# 28_PINS_PROJECT_Sheet1.net
KiCad netlist of a schematic drawn in Altium Designer
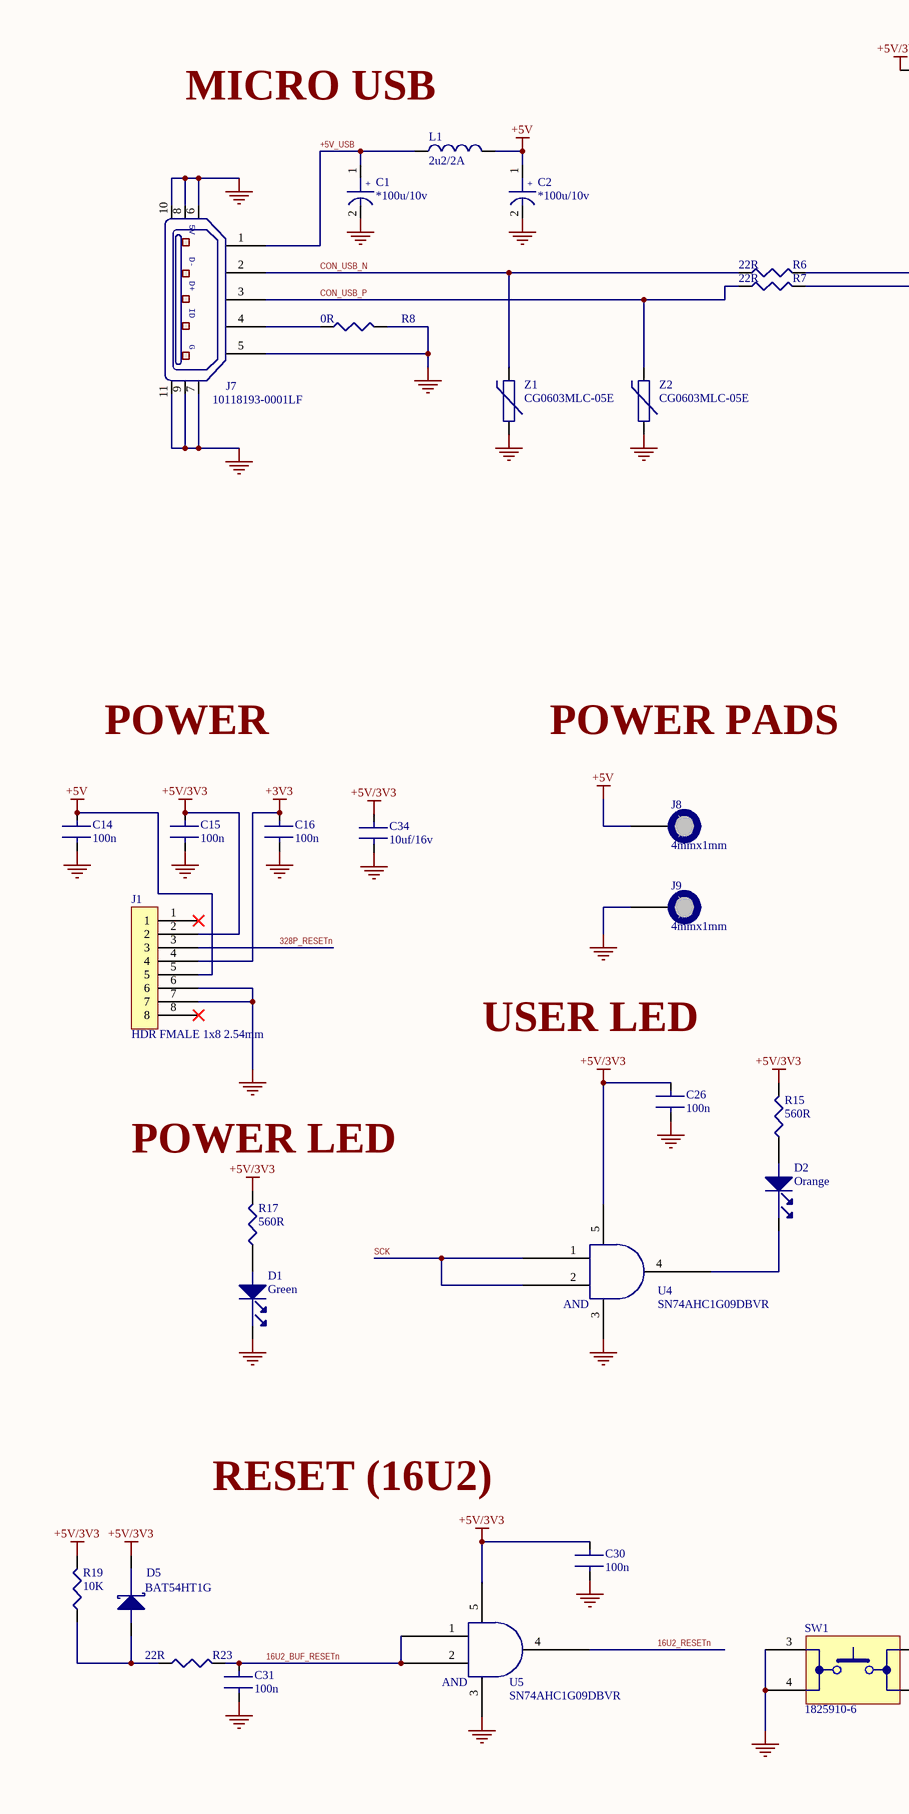
[diagram p0: 28_PINS_PROJECT_Sheet1.SchDoc, left]
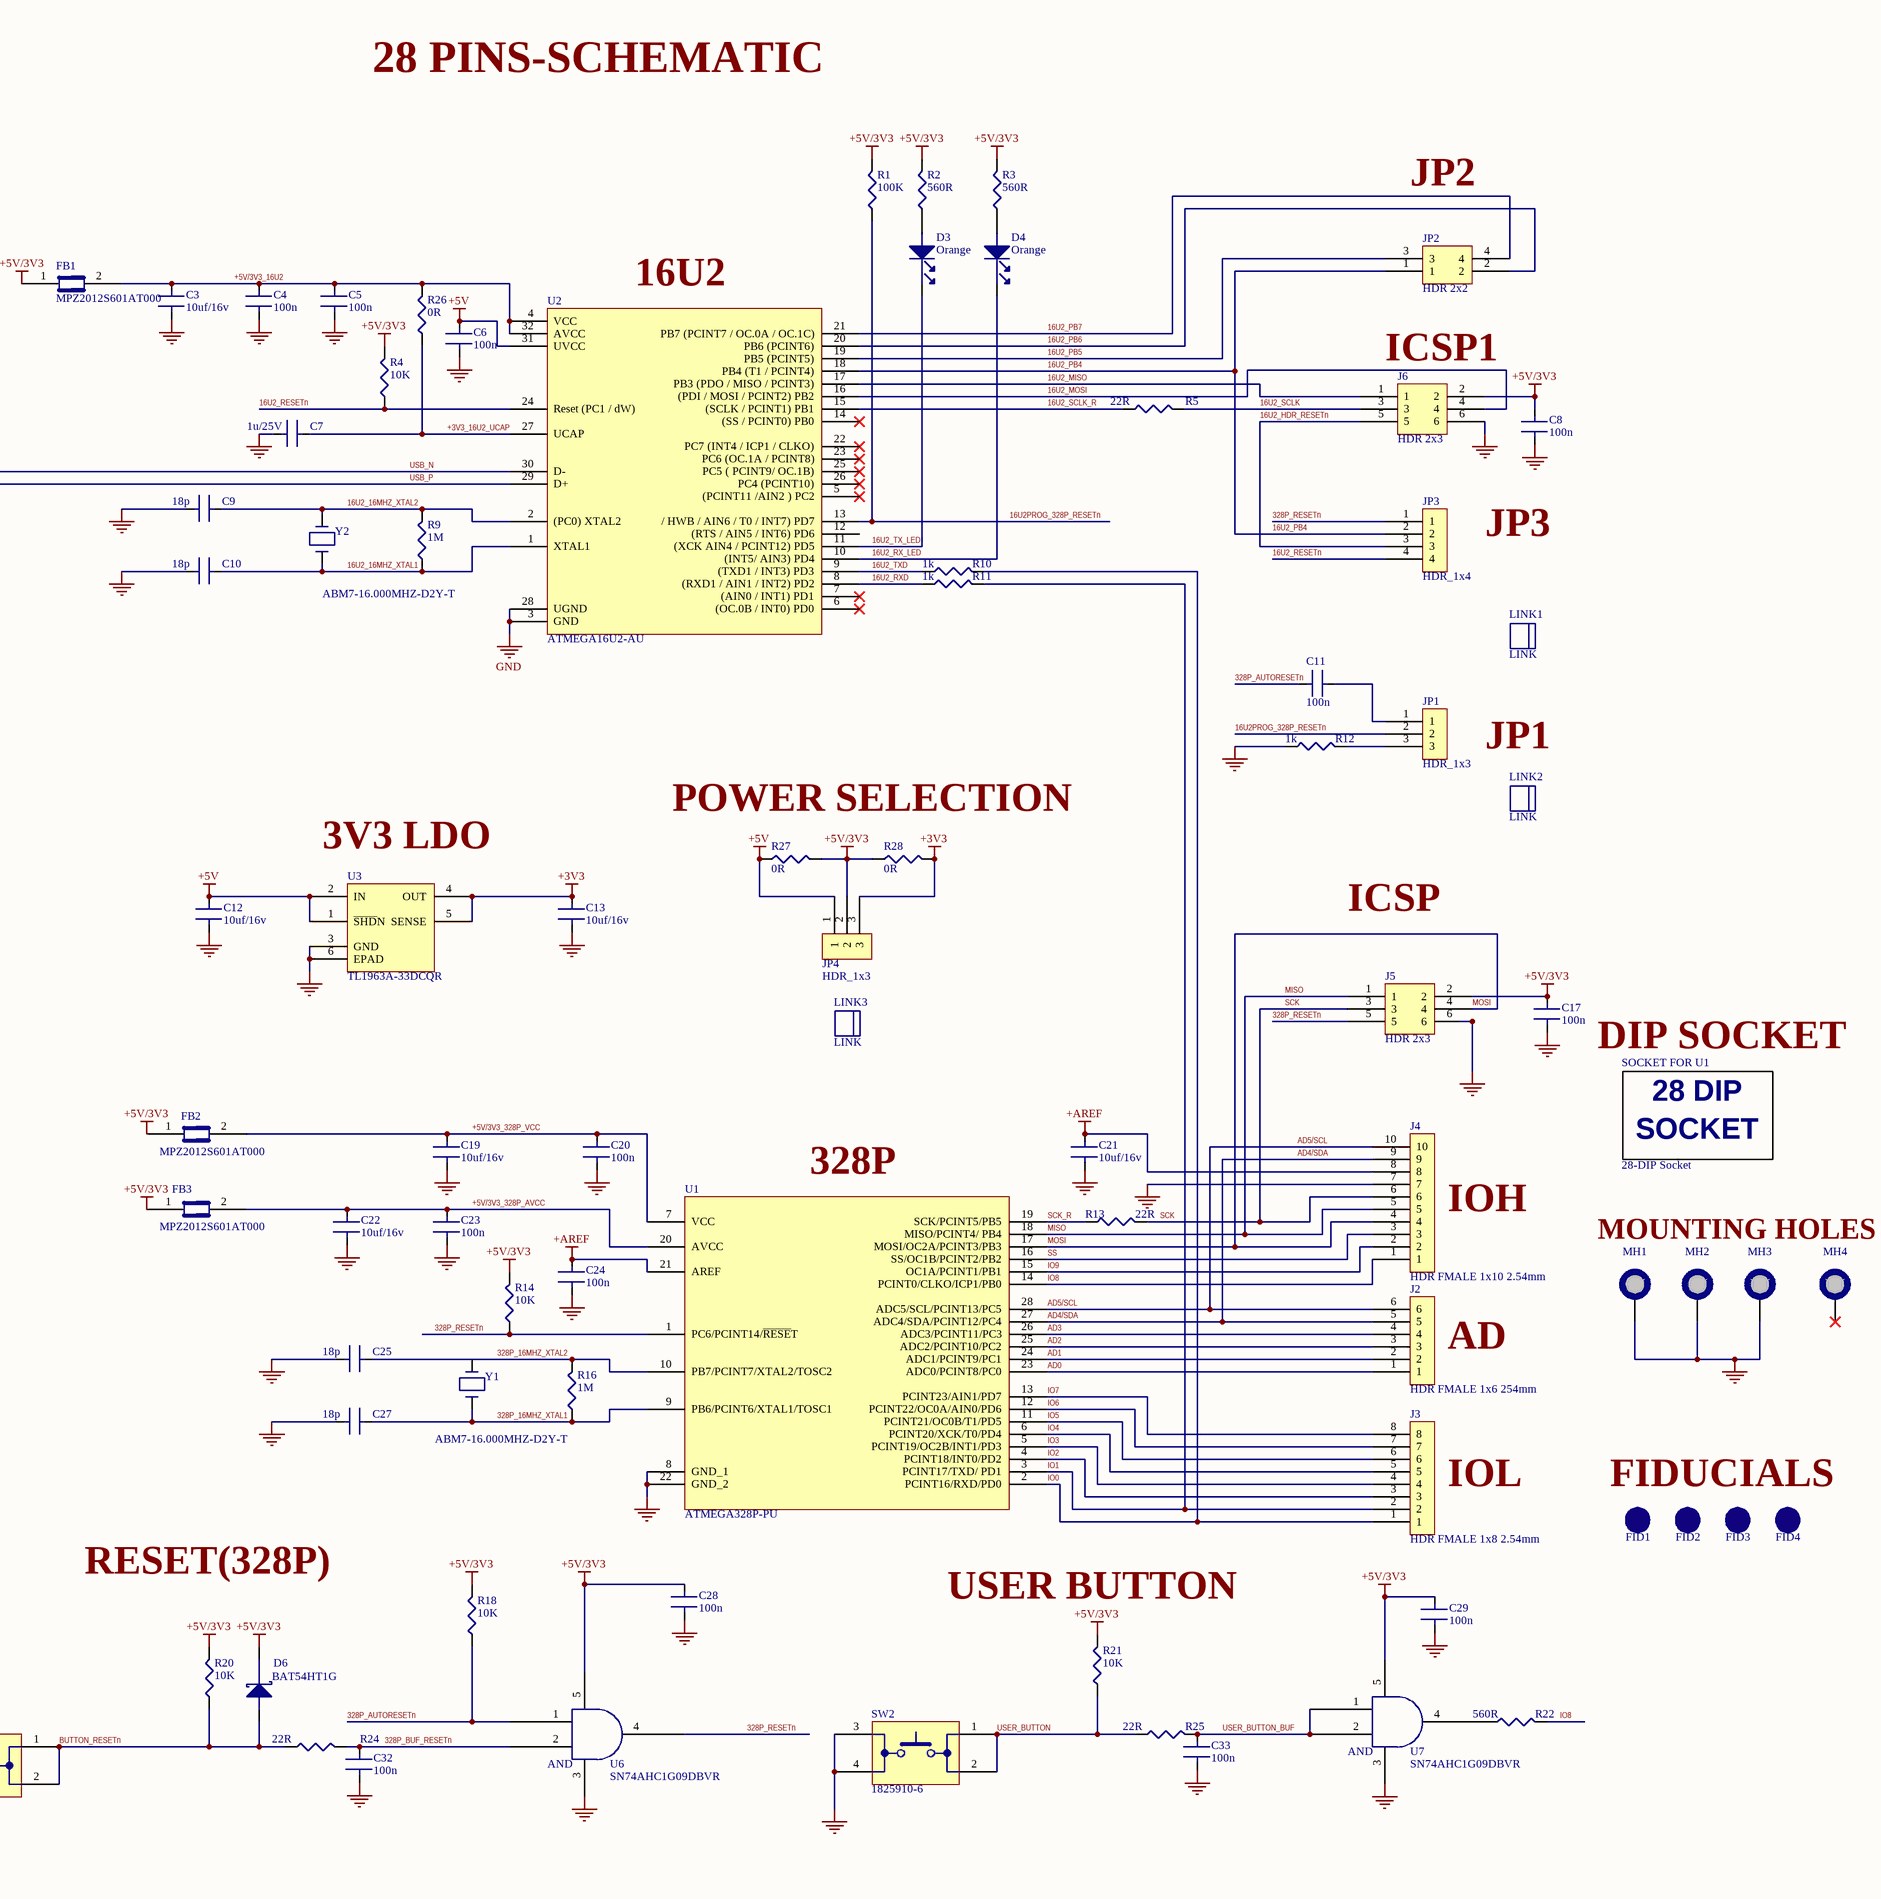
[diagram p1: 28_PINS_PROJECT_Sheet1.SchDoc, right]

(export (version "E")
  (design (tool "Eeschema 10.0.6"))
  (components
    (comp (ref "C1")
      (value "*100u/10v")
      (footprint "C_ALU_C_SIZE")
      (description "Cap Aluminum 100uF 10V 20% (5 X 5.4mm) SMD 50mA 1000 hr 85°C T/R")
      (fields
        (field (name "MANUFACTURER") "Panasonic")
        (field (name "MANUFACTURER PART NUMBER") "EEE-1AA101WR")
      )
      (libsource (lib "Schlib1") (part "EEE-1AA101WR"))
    )
    (comp (ref "C2")
      (value "*100u/10v")
      (footprint "C_ALU_C_SIZE")
      (description "Cap Aluminum 100uF 10V 20% (5 X 5.4mm) SMD 50mA 1000 hr 85°C T/R")
      (fields
        (field (name "MANUFACTURER") "Panasonic")
        (field (name "MANUFACTURER PART NUMBER") "EEE-1AA101WR")
      )
      (libsource (lib "Schlib1") (part "EEE-1AA101WR"))
    )
    (comp (ref "C3")
      (value "10uf/16v")
      (footprint "C0805")
      (fields
        (field (name "MANUFACTURER") "TDK")
        (field (name "MANUFACTURER PART NUMBER") "C2012X5R1C106M125AC")
        (field (name "TOLERANCE") "20%")
      )
      (libsource (lib "Schlib1") (part "C2012X5R1C106M125AC"))
    )
    (comp (ref "C4")
      (value "100n")
      (footprint "C0805")
      (fields
        (field (name "MANUFACTURER") "TDK")
        (field (name "MANUFACTURER PART NUMBER") "C2012X7R1H104K085AA")
        (field (name "TOLERANCE") "10%")
      )
      (libsource (lib "Schlib1") (part "C2012X7R1H104K085AA"))
    )
    (comp (ref "C5")
      (value "100n")
      (footprint "C0805")
      (fields
        (field (name "MANUFACTURER") "TDK")
        (field (name "MANUFACTURER PART NUMBER") "C2012X7R1H104K085AA")
        (field (name "TOLERANCE") "10%")
      )
      (libsource (lib "Schlib1") (part "C2012X7R1H104K085AA"))
    )
    (comp (ref "C6")
      (value "100n")
      (footprint "C0805")
      (fields
        (field (name "MANUFACTURER") "TDK")
        (field (name "MANUFACTURER PART NUMBER") "C2012X7R1H104K085AA")
        (field (name "TOLERANCE") "10%")
      )
      (libsource (lib "Schlib1") (part "C2012X7R1H104K085AA"))
    )
    (comp (ref "C7")
      (value "1u/25V")
      (footprint "C0805")
      (fields
        (field (name "MANUFACTURER") "TDK")
        (field (name "MANUFACTURER PART NUMBER") "C2012X5R1E105K125AA")
        (field (name "TOLERANCE") "10%")
      )
      (libsource (lib "Schlib1") (part "C2012X5R1E105K125AA"))
    )
    (comp (ref "C8")
      (value "100n")
      (footprint "C0805")
      (fields
        (field (name "MANUFACTURER") "TDK")
        (field (name "MANUFACTURER PART NUMBER") "C2012X7R1H104K085AA")
        (field (name "TOLERANCE") "10%")
      )
      (libsource (lib "Schlib1") (part "C2012X7R1H104K085AA"))
    )
    (comp (ref "C9")
      (value "18p")
      (footprint "C0805")
      (description "CAP CER 18PF 50V C0G/NP0 0805")
      (fields
        (field (name "MANUFACTURER") "KEMET")
        (field (name "MANUFACTURER PART NUMBER") "C0805C180J5GACTU")
      )
      (libsource (lib "Schlib1") (part "C0805C180J5GACTU"))
    )
    (comp (ref "C10")
      (value "18p")
      (footprint "C0805")
      (description "CAP CER 18PF 50V C0G/NP0 0805")
      (fields
        (field (name "MANUFACTURER") "KEMET")
        (field (name "MANUFACTURER PART NUMBER") "C0805C180J5GACTU")
      )
      (libsource (lib "Schlib1") (part "C0805C180J5GACTU"))
    )
    (comp (ref "C11")
      (value "100n")
      (footprint "C0805")
      (fields
        (field (name "MANUFACTURER") "TDK")
        (field (name "MANUFACTURER PART NUMBER") "C2012X7R1H104K085AA")
        (field (name "TOLERANCE") "10%")
      )
      (libsource (lib "Schlib1") (part "C2012X7R1H104K085AA"))
    )
    (comp (ref "C12")
      (value "10uf/16v")
      (footprint "C0805")
      (fields
        (field (name "MANUFACTURER") "TDK")
        (field (name "MANUFACTURER PART NUMBER") "C2012X5R1C106M125AC")
        (field (name "TOLERANCE") "20%")
      )
      (libsource (lib "Schlib1") (part "C2012X5R1C106M125AC"))
    )
    (comp (ref "C13")
      (value "10uf/16v")
      (footprint "C0805")
      (fields
        (field (name "MANUFACTURER") "TDK")
        (field (name "MANUFACTURER PART NUMBER") "C2012X5R1C106M125AC")
        (field (name "TOLERANCE") "20%")
      )
      (libsource (lib "Schlib1") (part "C2012X5R1C106M125AC"))
    )
    (comp (ref "C14")
      (value "100n")
      (footprint "C0805")
      (fields
        (field (name "MANUFACTURER") "TDK")
        (field (name "MANUFACTURER PART NUMBER") "C2012X7R1H104K085AA")
        (field (name "TOLERANCE") "10%")
      )
      (libsource (lib "Schlib1") (part "C2012X7R1H104K085AA"))
    )
    (comp (ref "C15")
      (value "100n")
      (footprint "C0805")
      (fields
        (field (name "MANUFACTURER") "TDK")
        (field (name "MANUFACTURER PART NUMBER") "C2012X7R1H104K085AA")
        (field (name "TOLERANCE") "10%")
      )
      (libsource (lib "Schlib1") (part "C2012X7R1H104K085AA"))
    )
    (comp (ref "C16")
      (value "100n")
      (footprint "C0805")
      (fields
        (field (name "MANUFACTURER") "TDK")
        (field (name "MANUFACTURER PART NUMBER") "C2012X7R1H104K085AA")
        (field (name "TOLERANCE") "10%")
      )
      (libsource (lib "Schlib1") (part "C2012X7R1H104K085AA"))
    )
    (comp (ref "C17")
      (value "100n")
      (footprint "C0805")
      (fields
        (field (name "MANUFACTURER") "TDK")
        (field (name "MANUFACTURER PART NUMBER") "C2012X7R1H104K085AA")
        (field (name "TOLERANCE") "10%")
      )
      (libsource (lib "Schlib1") (part "C2012X7R1H104K085AA"))
    )
    (comp (ref "C19")
      (value "10uf/16v")
      (footprint "C0805")
      (fields
        (field (name "MANUFACTURER") "TDK")
        (field (name "MANUFACTURER PART NUMBER") "C2012X5R1C106M125AC")
        (field (name "TOLERANCE") "20%")
      )
      (libsource (lib "Schlib1") (part "C2012X5R1C106M125AC"))
    )
    (comp (ref "C20")
      (value "100n")
      (footprint "C0805")
      (fields
        (field (name "MANUFACTURER") "TDK")
        (field (name "MANUFACTURER PART NUMBER") "C2012X7R1H104K085AA")
        (field (name "TOLERANCE") "10%")
      )
      (libsource (lib "Schlib1") (part "C2012X7R1H104K085AA"))
    )
    (comp (ref "C21")
      (value "10uf/16v")
      (footprint "C0805")
      (fields
        (field (name "MANUFACTURER") "TDK")
        (field (name "MANUFACTURER PART NUMBER") "C2012X5R1C106M125AC")
        (field (name "TOLERANCE") "20%")
      )
      (libsource (lib "Schlib1") (part "C2012X5R1C106M125AC"))
    )
    (comp (ref "C22")
      (value "10uf/16v")
      (footprint "C0805")
      (fields
        (field (name "MANUFACTURER") "TDK")
        (field (name "MANUFACTURER PART NUMBER") "C2012X5R1C106M125AC")
        (field (name "TOLERANCE") "20%")
      )
      (libsource (lib "Schlib1") (part "C2012X5R1C106M125AC"))
    )
    (comp (ref "C23")
      (value "100n")
      (footprint "C0805")
      (fields
        (field (name "MANUFACTURER") "TDK")
        (field (name "MANUFACTURER PART NUMBER") "C2012X7R1H104K085AA")
        (field (name "TOLERANCE") "10%")
      )
      (libsource (lib "Schlib1") (part "C2012X7R1H104K085AA"))
    )
    (comp (ref "C24")
      (value "100n")
      (footprint "C0805")
      (fields
        (field (name "MANUFACTURER") "TDK")
        (field (name "MANUFACTURER PART NUMBER") "C2012X7R1H104K085AA")
        (field (name "TOLERANCE") "10%")
      )
      (libsource (lib "Schlib1") (part "C2012X7R1H104K085AA"))
    )
    (comp (ref "C25")
      (value "18p")
      (footprint "C0805")
      (description "CAP CER 18PF 50V C0G/NP0 0805")
      (fields
        (field (name "MANUFACTURER") "KEMET")
        (field (name "MANUFACTURER PART NUMBER") "C0805C180J5GACTU")
      )
      (libsource (lib "Schlib1") (part "C0805C180J5GACTU"))
    )
    (comp (ref "C26")
      (value "100n")
      (footprint "C0805")
      (fields
        (field (name "MANUFACTURER") "TDK")
        (field (name "MANUFACTURER PART NUMBER") "C2012X7R1H104K085AA")
        (field (name "TOLERANCE") "10%")
      )
      (libsource (lib "Schlib1") (part "C2012X7R1H104K085AA"))
    )
    (comp (ref "C27")
      (value "18p")
      (footprint "C0805")
      (description "CAP CER 18PF 50V C0G/NP0 0805")
      (fields
        (field (name "MANUFACTURER") "KEMET")
        (field (name "MANUFACTURER PART NUMBER") "C0805C180J5GACTU")
      )
      (libsource (lib "Schlib1") (part "C0805C180J5GACTU"))
    )
    (comp (ref "C28")
      (value "100n")
      (footprint "C0805")
      (fields
        (field (name "MANUFACTURER") "TDK")
        (field (name "MANUFACTURER PART NUMBER") "C2012X7R1H104K085AA")
        (field (name "TOLERANCE") "10%")
      )
      (libsource (lib "Schlib1") (part "C2012X7R1H104K085AA"))
    )
    (comp (ref "C29")
      (value "100n")
      (footprint "C0805")
      (fields
        (field (name "MANUFACTURER") "TDK")
        (field (name "MANUFACTURER PART NUMBER") "C2012X7R1H104K085AA")
        (field (name "TOLERANCE") "10%")
      )
      (libsource (lib "Schlib1") (part "C2012X7R1H104K085AA"))
    )
    (comp (ref "C30")
      (value "100n")
      (footprint "C0805")
      (fields
        (field (name "MANUFACTURER") "TDK")
        (field (name "MANUFACTURER PART NUMBER") "C2012X7R1H104K085AA")
        (field (name "TOLERANCE") "10%")
      )
      (libsource (lib "Schlib1") (part "C2012X7R1H104K085AA"))
    )
    (comp (ref "C31")
      (value "100n")
      (footprint "C0805")
      (fields
        (field (name "MANUFACTURER") "TDK")
        (field (name "MANUFACTURER PART NUMBER") "C2012X7R1H104K085AA")
        (field (name "TOLERANCE") "10%")
      )
      (libsource (lib "Schlib1") (part "C2012X7R1H104K085AA"))
    )
    (comp (ref "C32")
      (value "100n")
      (footprint "C0805")
      (fields
        (field (name "MANUFACTURER") "TDK")
        (field (name "MANUFACTURER PART NUMBER") "C2012X7R1H104K085AA")
        (field (name "TOLERANCE") "10%")
      )
      (libsource (lib "Schlib1") (part "C2012X7R1H104K085AA"))
    )
    (comp (ref "C33")
      (value "100n")
      (footprint "C0805")
      (fields
        (field (name "MANUFACTURER") "TDK")
        (field (name "MANUFACTURER PART NUMBER") "C2012X7R1H104K085AA")
        (field (name "TOLERANCE") "10%")
      )
      (libsource (lib "Schlib1") (part "C2012X7R1H104K085AA"))
    )
    (comp (ref "C34")
      (value "10uf/16v")
      (footprint "C0805")
      (fields
        (field (name "MANUFACTURER") "TDK")
        (field (name "MANUFACTURER PART NUMBER") "C2012X5R1C106M125AC")
        (field (name "TOLERANCE") "20%")
      )
      (libsource (lib "Schlib1") (part "C2012X5R1C106M125AC"))
    )
    (comp (ref "D1")
      (value "Green")
      (footprint "led_0603")
      (description "LED Uni-Color Green 572nm 2-Pin Chip 0603(1608Metric) T/R")
      (fields
        (field (name "MANUFACTURER") "Osram Opto")
        (field (name "MANUFACTURER PART NUMBER") "LGL29K-G2J1-24-Z")
      )
      (libsource (lib "Schlib1") (part "LGL29K-G2J1-24-Z"))
    )
    (comp (ref "D2")
      (value "Orange")
      (footprint "led_0603")
      (description "OSRAM - LO L29K-H2K1-24-Z - SMARTLED 0603 ORANGE")
      (fields
        (field (name "MANUFACTURER") "Osram Opto")
        (field (name "MANUFACTURER PART NUMBER") "LOL29K-H2K1-24-Z")
      )
      (libsource (lib "Schlib1") (part "LOL29K-H2K1-24-Z"))
    )
    (comp (ref "D3")
      (value "Orange")
      (footprint "led_0603")
      (description "OSRAM - LO L29K-H2K1-24-Z - SMARTLED 0603 ORANGE")
      (fields
        (field (name "MANUFACTURER") "Osram Opto")
        (field (name "MANUFACTURER PART NUMBER") "LOL29K-H2K1-24-Z")
      )
      (libsource (lib "Schlib1") (part "LOL29K-H2K1-24-Z"))
    )
    (comp (ref "D4")
      (value "Orange")
      (footprint "led_0603")
      (description "OSRAM - LO L29K-H2K1-24-Z - SMARTLED 0603 ORANGE")
      (fields
        (field (name "MANUFACTURER") "Osram Opto")
        (field (name "MANUFACTURER PART NUMBER") "LOL29K-H2K1-24-Z")
      )
      (libsource (lib "Schlib1") (part "LOL29K-H2K1-24-Z"))
    )
    (comp (ref "D5")
      (value "BAT54HT1G")
      (footprint "SOD323")
      (description "Small Signal Schottky Diode, Single, 30 V, 200 mA, 800 mV, 600 mA, 150 C ;RoHS Compliant: Yes")
      (fields (field (name "MANUFACTURER") "ON Semiconductor / Fairchild"))
      (libsource (lib "Schlib1") (part "BAT54HT1G"))
    )
    (comp (ref "D6")
      (value "BAT54HT1G")
      (footprint "SOD323")
      (description "Small Signal Schottky Diode, Single, 30 V, 200 mA, 800 mV, 600 mA, 150 C ;RoHS Compliant: Yes")
      (fields (field (name "MANUFACTURER") "ON Semiconductor / Fairchild"))
      (libsource (lib "Schlib1") (part "BAT54HT1G"))
    )
    (comp (ref "FB1")
      (value "MPZ2012S601AT000")
      (footprint "C0805")
      (description "FERRITE BEAD 600 OHM 0805 1LN")
      (fields (field (name "MANUFACTURER") "TDK"))
      (libsource (lib "Schlib1") (part "MPZ2012S601AT000"))
    )
    (comp (ref "FB2")
      (value "MPZ2012S601AT000")
      (footprint "C0805")
      (description "FERRITE BEAD 600 OHM 0805 1LN")
      (fields (field (name "MANUFACTURER") "TDK"))
      (libsource (lib "Schlib1") (part "MPZ2012S601AT000"))
    )
    (comp (ref "FB3")
      (value "MPZ2012S601AT000")
      (footprint "C0805")
      (description "FERRITE BEAD 600 OHM 0805 1LN")
      (fields (field (name "MANUFACTURER") "TDK"))
      (libsource (lib "Schlib1") (part "MPZ2012S601AT000"))
    )
    (comp (ref "FID1")
      (value "FID_1MMC")
      (footprint "FID_40x20D")
      (description "FIDUCIAL 40mil diameter 120 mil mask")
      (libsource (lib "Schlib1") (part "FID_1MMC"))
    )
    (comp (ref "FID2")
      (value "FID_1MMC")
      (footprint "FID_40x20D")
      (description "FIDUCIAL 40mil diameter 120 mil mask")
      (libsource (lib "Schlib1") (part "FID_1MMC"))
    )
    (comp (ref "FID3")
      (value "FID_1MMC")
      (footprint "FID_40x20D")
      (description "FIDUCIAL 40mil diameter 120 mil mask")
      (libsource (lib "Schlib1") (part "FID_1MMC"))
    )
    (comp (ref "FID4")
      (value "FID_1MMC")
      (footprint "FID_40x20D")
      (description "FIDUCIAL 40mil diameter 120 mil mask")
      (libsource (lib "Schlib1") (part "FID_1MMC"))
    )
    (comp (ref "J1")
      (value "HDR FMALE 1x8 2.54mm")
      (footprint "hdr_fmale_1x8_2.54mm")
      (description "2.54mm (0.1\") Pitch SIL Vertical PC Tail Socket Assembly, selective gold + tin, 8 contacts")
      (fields (field (name "MANUFACTURER") "Harwin") (field (name "MANUFACTURER PART NUMBER") "M20-7820842"))
      (libsource (lib "Schlib1") (part "M20-7820842"))
    )
    (comp (ref "J2")
      (value "HDR FMALE 1x6 254mm")
      (footprint "hdr_fmale_1x6_2.54mm")
      (description "06-WAY SIL VERT SOCKET L/FREE")
      (fields (field (name "MANUFACTURER") "Harwin") (field (name "MANUFACTURER PART NUMBER") "M20-7820646"))
      (libsource (lib "Schlib1") (part "M20-7820646"))
    )
    (comp (ref "J3")
      (value "HDR FMALE 1x8 2.54mm")
      (footprint "hdr_fmale_1x8_2.54mm")
      (description "2.54mm (0.1\") Pitch SIL Vertical PC Tail Socket Assembly, selective gold + tin, 8 contacts")
      (fields (field (name "MANUFACTURER") "Harwin") (field (name "MANUFACTURER PART NUMBER") "M20-7820842"))
      (libsource (lib "") (part "M20-7820842_1"))
    )
    (comp (ref "J4")
      (value "HDR FMALE 1x10 2.54mm")
      (footprint "hdr_fmale_1x10_2.54mm")
      (fields (field (name "MANUFACTURER") "Harwin") (field (name "MANUFACTURER PART NUMBER") "M20-7821046"))
      (libsource (lib "Schlib1") (part "M20-7821046"))
    )
    (comp (ref "J5")
      (value "HDR 2x3")
      (footprint "hdr_2x3_2.54mm")
      (description "CONN HEADER 6POS .100 STR 30AU")
      (fields
        (field (name "MANUFACTURER") "Amphenol FCI")
        (field (name "MANUFACTURER PART NUMBER") "67997-106HLF")
      )
      (libsource (lib "Schlib1") (part "67997-106HLF"))
    )
    (comp (ref "J6")
      (value "HDR 2x3")
      (footprint "hdr_2x3_2.54mm")
      (description "CONN HEADER 6POS .100 STR 30AU")
      (fields
        (field (name "MANUFACTURER") "Amphenol FCI")
        (field (name "MANUFACTURER PART NUMBER") "67997-106HLF")
      )
      (libsource (lib "Schlib1") (part "67997-106HLF"))
    )
    (comp (ref "J7")
      (value "10118193-0001LF")
      (footprint "10118193")
      (description "CONN USB MICRO B RECPT SMT R/A")
      (fields (field (name "MANUFACTURER") "Amphenol FCI"))
      (libsource (lib "28_PINS_PROJECT_Schlib1") (part "10118193-0001LF"))
    )
    (comp (ref "J8")
      (value "4mmx1mm")
      (footprint "PAD_WITH_HOLE_4MMx1.5MM")
      (description "Pad with hole 4mm x 1mm")
      (libsource (lib "Schlib1") (part "PAD_WITH_HOLE_4MMx1.5MM"))
    )
    (comp (ref "J9")
      (value "4mmx1mm")
      (footprint "PAD_WITH_HOLE_4MMx1.5MM")
      (description "Pad with hole 4mm x 1mm")
      (libsource (lib "Schlib1") (part "PAD_WITH_HOLE_4MMx1.5MM"))
    )
    (comp (ref "JP1")
      (value "HDR_1x3")
      (footprint "hdr_1x3_2.54mm")
      (description "Conn Unshrouded Header HDR 3 POS 2.54mm Solder ST Thru-Hole Bulk")
      (fields
        (field (name "MANUFACTURER") "Amphenol FCI")
        (field (name "MANUFACTURER PART NUMBER") "68000-103HLF")
      )
      (libsource (lib "Schlib1") (part "68000-103HLF"))
    )
    (comp (ref "JP2")
      (value "HDR 2x2")
      (footprint "hdr_2x2_2.54mm")
      (description "CONN HEADER VERT 4POS 2.54MM")
      (fields
        (field (name "MANUFACTURER") "Amphenol FCI")
        (field (name "MANUFACTURER PART NUMBER") "68602-204HLF")
      )
      (libsource (lib "Schlib1") (part "68602-204HLF"))
    )
    (comp (ref "JP3")
      (value "HDR_1x4")
      (footprint "hdr_1x4_2.54mm")
      (description "CONN HEADER VERT 4POS 2.54MM")
      (fields
        (field (name "MANUFACTURER") "Amphenol FCI")
        (field (name "MANUFACTURER PART NUMBER") "68001-204HLF")
      )
      (libsource (lib "Schlib1") (part "68001-204HLF"))
    )
    (comp (ref "JP4")
      (value "HDR_1x3")
      (footprint "hdr_1x3_2.54mm")
      (description "Conn Unshrouded Header HDR 3 POS 2.54mm Solder ST Thru-Hole Bulk")
      (fields
        (field (name "MANUFACTURER") "Amphenol FCI")
        (field (name "MANUFACTURER PART NUMBER") "68000-103HLF")
      )
      (libsource (lib "") (part "68000-103HLF_1"))
    )
    (comp (ref "L1")
      (value "2u2/2A")
      (footprint "C1210_IND")
      (description "FIXED IND 2.2UH 2A 80 MOHM SMD")
      (fields
        (field (name "MANUFACTURER") "KEMET")
        (field (name "MANUFACTURER PART NUMBER") "L1210R2R2MDWIT")
      )
      (libsource (lib "Schlib1") (part "L1210R2R2MDWIT"))
    )
    (comp (ref "LINK1")
      (value "LINK")
      (description "CONN JUMPER SHORTING .100\" GOLD")
      (fields
        (field (name "MANUFACTURER") "Sullins")
        (field (name "MANUFACTURER PART NUMBER") "QPC02SXGN-RC")
      )
      (libsource (lib "Schlib1") (part "QPC02SXGN-RC"))
    )
    (comp (ref "LINK2")
      (value "LINK")
      (description "CONN JUMPER SHORTING .100\" GOLD")
      (fields
        (field (name "MANUFACTURER") "Sullins")
        (field (name "MANUFACTURER PART NUMBER") "QPC02SXGN-RC")
      )
      (libsource (lib "Schlib1") (part "QPC02SXGN-RC"))
    )
    (comp (ref "LINK3")
      (value "LINK")
      (description "CONN JUMPER SHORTING .100\" GOLD")
      (fields
        (field (name "MANUFACTURER") "Sullins")
        (field (name "MANUFACTURER PART NUMBER") "QPC02SXGN-RC")
      )
      (libsource (lib "Schlib1") (part "QPC02SXGN-RC"))
    )
    (comp (ref "MH1")
      (value "MH_7.4MMC_3.2MMD")
      (footprint "MH_7.4MMC_3.2MMD")
      (description "Mounting Hole 7.4 diameter 3.2 drill")
      (libsource (lib "Schlib1") (part "MH_7.4MMC_3.2MMD"))
    )
    (comp (ref "MH2")
      (value "MH_7.4MMC_3.2MMD")
      (footprint "MH_7.4MMC_3.2MMD")
      (description "Mounting Hole 7.4 diameter 3.2 drill")
      (libsource (lib "Schlib1") (part "MH_7.4MMC_3.2MMD"))
    )
    (comp (ref "MH3")
      (value "MH_7.4MMC_3.2MMD")
      (footprint "MH_7.4MMC_3.2MMD")
      (description "Mounting Hole 7.4 diameter 3.2 drill")
      (libsource (lib "Schlib1") (part "MH_7.4MMC_3.2MMD"))
    )
    (comp (ref "MH4")
      (value "MH_7.4MMNC_3.2MMD")
      (footprint "MH_7.4MMD_3.2MMD_NON_COPPER_NPTH")
      (description "Hole 7.4mm diameter (non copper) 3,2 mm drill NPTH")
      (libsource (lib "Schlib1") (part "MH_7.4MMNC_3.2MMD"))
    )
    (comp (ref "R1")
      (value "100K")
      (footprint "R0805")
      (description "YAGEO         RC0805FR-07100KL            RES, THICK FILM, 100K, 1%, 0.125W, 0805, REEL")
      (fields
        (field (name "MANUFACTURER") "Yageo")
        (field (name "MANUFACTURER PART NUMBER") "RC0805FR-07100KL")
      )
      (libsource (lib "Schlib1") (part "RC0805FR-07100KL"))
    )
    (comp (ref "R2")
      (value "560R")
      (footprint "R0805")
      (description "Surface Mount Thick Film Resistor, RC Series, 560 ohm, 125 mW, - 1%, 150 V, 0805 [2012 Metric]")
      (fields
        (field (name "MANUFACTURER") "Yageo")
        (field (name "MANUFACTURER PART NUMBER") "RC0805FR-07560RL")
      )
      (libsource (lib "Schlib1") (part "RC0805FR-07560RL"))
    )
    (comp (ref "R3")
      (value "560R")
      (footprint "R0805")
      (description "Surface Mount Thick Film Resistor, RC Series, 560 ohm, 125 mW, - 1%, 150 V, 0805 [2012 Metric]")
      (fields
        (field (name "MANUFACTURER") "Yageo")
        (field (name "MANUFACTURER PART NUMBER") "RC0805FR-07560RL")
      )
      (libsource (lib "Schlib1") (part "RC0805FR-07560RL"))
    )
    (comp (ref "R4")
      (value "10K")
      (footprint "R0805")
      (description "RES SMD 10K OHM 1% 1/8W 0805")
      (fields
        (field (name "MANUFACTURER") "Yageo")
        (field (name "MANUFACTURER PART NUMBER") "RC0805FR-0710KL")
      )
      (libsource (lib "Schlib1") (part "RC0805FR-0710KL"))
    )
    (comp (ref "R5")
      (value "22R")
      (footprint "R0805")
      (description "RES SMD 22 OHM 1% 1/8W 0805")
      (fields
        (field (name "MANUFACTURER") "Yageo")
        (field (name "MANUFACTURER PART NUMBER") "RC0805FR-0722RL")
      )
      (libsource (lib "Schlib1") (part "RC0805FR-0722RL"))
    )
    (comp (ref "R6")
      (value "22R")
      (footprint "R0805")
      (description "RES SMD 22 OHM 1% 1/8W 0805")
      (fields
        (field (name "MANUFACTURER") "Yageo")
        (field (name "MANUFACTURER PART NUMBER") "RC0805FR-0722RL")
      )
      (libsource (lib "Schlib1") (part "RC0805FR-0722RL"))
    )
    (comp (ref "R7")
      (value "22R")
      (footprint "R0805")
      (description "RES SMD 22 OHM 1% 1/8W 0805")
      (fields
        (field (name "MANUFACTURER") "Yageo")
        (field (name "MANUFACTURER PART NUMBER") "RC0805FR-0722RL")
      )
      (libsource (lib "Schlib1") (part "RC0805FR-0722RL"))
    )
    (comp (ref "R8")
      (value "0R")
      (footprint "R0805")
      (description "Surface Mount Thick Film Resistor, RC Series, 125 mW, - 5%, 150 V, 0805 [2012 Metric]")
      (fields
        (field (name "MANUFACTURER") "Yageo")
        (field (name "MANUFACTURER PART NUMBER") "RC0805JR-070RL")
      )
      (libsource (lib "Schlib1") (part "RC0805JR-070RL"))
    )
    (comp (ref "R9")
      (value "1M")
      (footprint "R0805")
      (description "Res Thick Film 0805 1M Ohm 1% 0.125W(1/8W) ±100ppm/C Epoxy SMD T/R")
      (fields
        (field (name "MANUFACTURER") "Yageo Phycomp")
        (field (name "MANUFACTURER PART NUMBER") "RC0805FR-071ML")
      )
      (libsource (lib "Schlib1") (part "RC0805FR-071ML"))
    )
    (comp (ref "R10")
      (value "1k")
      (footprint "R0805")
      (description "Res Thick Film 0805 1K Ohm 1% 1/8W ?100ppm/C Molded SMD SMD Paper T/R")
      (fields
        (field (name "MANUFACTURER") "Yageo Phycomp")
        (field (name "MANUFACTURER PART NUMBER") "RC0805FR-071KL")
      )
      (libsource (lib "Schlib1") (part "RC0805FR-071KL"))
    )
    (comp (ref "R11")
      (value "1k")
      (footprint "R0805")
      (description "Res Thick Film 0805 1K Ohm 1% 1/8W ?100ppm/C Molded SMD SMD Paper T/R")
      (fields
        (field (name "MANUFACTURER") "Yageo Phycomp")
        (field (name "MANUFACTURER PART NUMBER") "RC0805FR-071KL")
      )
      (libsource (lib "Schlib1") (part "RC0805FR-071KL"))
    )
    (comp (ref "R12")
      (value "1k")
      (footprint "R0805")
      (description "Res Thick Film 0805 1K Ohm 1% 1/8W ?100ppm/C Molded SMD SMD Paper T/R")
      (fields
        (field (name "MANUFACTURER") "Yageo Phycomp")
        (field (name "MANUFACTURER PART NUMBER") "RC0805FR-071KL")
      )
      (libsource (lib "Schlib1") (part "RC0805FR-071KL"))
    )
    (comp (ref "R13")
      (value "22R")
      (footprint "R0805")
      (description "RES SMD 22 OHM 1% 1/8W 0805")
      (fields
        (field (name "MANUFACTURER") "Yageo")
        (field (name "MANUFACTURER PART NUMBER") "RC0805FR-0722RL")
      )
      (libsource (lib "Schlib1") (part "RC0805FR-0722RL"))
    )
    (comp (ref "R14")
      (value "10K")
      (footprint "R0805")
      (description "RES SMD 10K OHM 1% 1/8W 0805")
      (fields
        (field (name "MANUFACTURER") "Yageo")
        (field (name "MANUFACTURER PART NUMBER") "RC0805FR-0710KL")
      )
      (libsource (lib "Schlib1") (part "RC0805FR-0710KL"))
    )
    (comp (ref "R15")
      (value "560R")
      (footprint "R0805")
      (description "Surface Mount Thick Film Resistor, RC Series, 560 ohm, 125 mW, - 1%, 150 V, 0805 [2012 Metric]")
      (fields
        (field (name "MANUFACTURER") "Yageo")
        (field (name "MANUFACTURER PART NUMBER") "RC0805FR-07560RL")
      )
      (libsource (lib "Schlib1") (part "RC0805FR-07560RL"))
    )
    (comp (ref "R16")
      (value "1M")
      (footprint "R0805")
      (description "Res Thick Film 0805 1M Ohm 1% 0.125W(1/8W) ±100ppm/C Epoxy SMD T/R")
      (fields
        (field (name "MANUFACTURER") "Yageo Phycomp")
        (field (name "MANUFACTURER PART NUMBER") "RC0805FR-071ML")
      )
      (libsource (lib "Schlib1") (part "RC0805FR-071ML"))
    )
    (comp (ref "R17")
      (value "560R")
      (footprint "R0805")
      (description "Surface Mount Thick Film Resistor, RC Series, 560 ohm, 125 mW, - 1%, 150 V, 0805 [2012 Metric]")
      (fields
        (field (name "MANUFACTURER") "Yageo")
        (field (name "MANUFACTURER PART NUMBER") "RC0805FR-07560RL")
      )
      (libsource (lib "Schlib1") (part "RC0805FR-07560RL"))
    )
    (comp (ref "R18")
      (value "10K")
      (footprint "R0805")
      (description "RES SMD 10K OHM 1% 1/8W 0805")
      (fields
        (field (name "MANUFACTURER") "Yageo")
        (field (name "MANUFACTURER PART NUMBER") "RC0805FR-0710KL")
      )
      (libsource (lib "Schlib1") (part "RC0805FR-0710KL"))
    )
    (comp (ref "R19")
      (value "10K")
      (footprint "R0805")
      (description "RES SMD 10K OHM 1% 1/8W 0805")
      (fields
        (field (name "MANUFACTURER") "Yageo")
        (field (name "MANUFACTURER PART NUMBER") "RC0805FR-0710KL")
      )
      (libsource (lib "Schlib1") (part "RC0805FR-0710KL"))
    )
    (comp (ref "R20")
      (value "10K")
      (footprint "R0805")
      (description "RES SMD 10K OHM 1% 1/8W 0805")
      (fields
        (field (name "MANUFACTURER") "Yageo")
        (field (name "MANUFACTURER PART NUMBER") "RC0805FR-0710KL")
      )
      (libsource (lib "Schlib1") (part "RC0805FR-0710KL"))
    )
    (comp (ref "R21")
      (value "10K")
      (footprint "R0805")
      (description "RES SMD 10K OHM 1% 1/8W 0805")
      (fields
        (field (name "MANUFACTURER") "Yageo")
        (field (name "MANUFACTURER PART NUMBER") "RC0805FR-0710KL")
      )
      (libsource (lib "Schlib1") (part "RC0805FR-0710KL"))
    )
    (comp (ref "R22")
      (value "560R")
      (footprint "R0805")
      (description "Surface Mount Thick Film Resistor, RC Series, 560 ohm, 125 mW, - 1%, 150 V, 0805 [2012 Metric]")
      (fields
        (field (name "MANUFACTURER") "Yageo")
        (field (name "MANUFACTURER PART NUMBER") "RC0805FR-07560RL")
      )
      (libsource (lib "Schlib1") (part "RC0805FR-07560RL"))
    )
    (comp (ref "R23")
      (value "22R")
      (footprint "R0805")
      (description "RES SMD 22 OHM 1% 1/8W 0805")
      (fields
        (field (name "MANUFACTURER") "Yageo")
        (field (name "MANUFACTURER PART NUMBER") "RC0805FR-0722RL")
      )
      (libsource (lib "Schlib1") (part "RC0805FR-0722RL"))
    )
    (comp (ref "R24")
      (value "22R")
      (footprint "R0805")
      (description "RES SMD 22 OHM 1% 1/8W 0805")
      (fields
        (field (name "MANUFACTURER") "Yageo")
        (field (name "MANUFACTURER PART NUMBER") "RC0805FR-0722RL")
      )
      (libsource (lib "Schlib1") (part "RC0805FR-0722RL"))
    )
    (comp (ref "R25")
      (value "22R")
      (footprint "R0805")
      (description "RES SMD 22 OHM 1% 1/8W 0805")
      (fields
        (field (name "MANUFACTURER") "Yageo")
        (field (name "MANUFACTURER PART NUMBER") "RC0805FR-0722RL")
      )
      (libsource (lib "Schlib1") (part "RC0805FR-0722RL"))
    )
    (comp (ref "R26")
      (value "0R")
      (footprint "R0805")
      (description "Surface Mount Thick Film Resistor, RC Series, 125 mW, - 5%, 150 V, 0805 [2012 Metric]")
      (fields
        (field (name "MANUFACTURER") "Yageo")
        (field (name "MANUFACTURER PART NUMBER") "RC0805JR-070RL")
      )
      (libsource (lib "Schlib1") (part "RC0805JR-070RL"))
    )
    (comp (ref "R27")
      (value "0R")
      (footprint "R0805")
      (description "Surface Mount Thick Film Resistor, RC Series, 125 mW, - 5%, 150 V, 0805 [2012 Metric]")
      (fields
        (field (name "MANUFACTURER") "Yageo")
        (field (name "MANUFACTURER PART NUMBER") "RC0805JR-070RL")
      )
      (libsource (lib "Schlib1") (part "RC0805JR-070RL"))
    )
    (comp (ref "R28")
      (value "0R")
      (footprint "R0805")
      (description "Surface Mount Thick Film Resistor, RC Series, 125 mW, - 5%, 150 V, 0805 [2012 Metric]")
      (fields
        (field (name "MANUFACTURER") "Yageo")
        (field (name "MANUFACTURER PART NUMBER") "RC0805JR-070RL")
      )
      (libsource (lib "Schlib1") (part "RC0805JR-070RL"))
    )
    (comp (ref "SOCKET FOR U1")
      (value "28-DIP Socket")
      (footprint "28_DIP_7.62mm_SOCKET")
      (description "CONN IC DIP SOCKET 28POS TIN")
      (fields (field (name "MANUFACTURER") "3M") (field (name "MANUFACTURER PART NUMBER") "4828-3004-CP"))
      (libsource (lib "28_PINS_PROJECT_Schlib1") (part "4828-3004-CP"))
    )
    (comp (ref "SW1")
      (value "1825910-6")
      (footprint "1825910-6")
      (description "SWITCH TACTILE SPST-NO 0.05A 24V")
      (fields (field (name "MANUFACTURER") "TE Connectivity Alcoswitch"))
      (libsource (lib "Schlib1") (part "1825910-6"))
    )
    (comp (ref "SW2")
      (value "1825910-6")
      (footprint "1825910-6")
      (description "SWITCH TACTILE SPST-NO 0.05A 24V")
      (fields (field (name "MANUFACTURER") "TE Connectivity Alcoswitch"))
      (libsource (lib "Schlib1") (part "1825910-6"))
    )
    (comp (ref "U1")
      (value "ATMEGA328P-PU")
      (footprint "28_DIP_7.62mm")
      (description "ATMEGA328P-PU; 8 bit Microcontroller AVR 20MHz 1; 32kb Flash; 2kb RAM; I2C SPI 2")
      (fields (field (name "MANUFACTURER") "Microchip"))
      (libsource (lib "28_PINS_PROJECT_Schlib1") (part "ATMEGA328P-PU"))
    )
    (comp (ref "U2")
      (value "ATMEGA16U2-AU")
      (footprint "TQFP32")
      (description "MICROCHIP - ATMEGA16U2-AU - MCU, 8BIT, MEGAAVR, 16MHZ, TQFP-32")
      (fields (field (name "MANUFACTURER") "Microchip / Atmel"))
      (libsource (lib "28_PINS_PROJECT_Schlib1") (part "ATMEGA16U2-AU"))
    )
    (comp (ref "U3")
      (value "TL1963A-33DCQR")
      (footprint "DCQ(R-PDSO-G6)")
      (description "IC REG LINEAR 3.3V 1.5A SOT223-6")
      (fields (field (name "MANUFACTURER") "Texas Instruments"))
      (libsource (lib "Schlib1") (part "TL1963A-33DCQR"))
    )
    (comp (ref "U4")
      (value "SN74AHC1G09DBVR")
      (footprint "DBV_SOT_23_5")
      (description "TEXAS INSTRUMENTS - SN74AHC1G09DBVR - AND Gate, 74AHC1G09, 2 Input, 2 V to 5.5 V, SOT-23-5")
      (fields (field (name "MANUFACTURER") "Texas Instruments"))
      (libsource (lib "Schlib1") (part "SN74AHC1G09DBVR"))
    )
    (comp (ref "U5")
      (value "SN74AHC1G09DBVR")
      (footprint "DBV_SOT_23_5")
      (description "TEXAS INSTRUMENTS - SN74AHC1G09DBVR - AND Gate, 74AHC1G09, 2 Input, 2 V to 5.5 V, SOT-23-5")
      (fields (field (name "MANUFACTURER") "Texas Instruments"))
      (libsource (lib "Schlib1") (part "SN74AHC1G09DBVR"))
    )
    (comp (ref "U6")
      (value "SN74AHC1G09DBVR")
      (footprint "DBV_SOT_23_5")
      (description "TEXAS INSTRUMENTS - SN74AHC1G09DBVR - AND Gate, 74AHC1G09, 2 Input, 2 V to 5.5 V, SOT-23-5")
      (fields (field (name "MANUFACTURER") "Texas Instruments"))
      (libsource (lib "Schlib1") (part "SN74AHC1G09DBVR"))
    )
    (comp (ref "U7")
      (value "SN74AHC1G09DBVR")
      (footprint "DBV_SOT_23_5")
      (description "TEXAS INSTRUMENTS - SN74AHC1G09DBVR - AND Gate, 74AHC1G09, 2 Input, 2 V to 5.5 V, SOT-23-5")
      (fields (field (name "MANUFACTURER") "Texas Instruments"))
      (libsource (lib "Schlib1") (part "SN74AHC1G09DBVR"))
    )
    (comp (ref "Y1")
      (value "ABM7-16.000MHZ-D2Y-T")
      (footprint "16mhz_crystal")
      (description "CRYSTAL 16.0000MHZ 18PF SMD")
      (fields (field (name "MANUFACTURER") "Abracon") (field (name "TOLERANCE") "20ppm"))
      (libsource (lib "Schlib1") (part "ABM7-16.000MHZ-D2Y-T"))
    )
    (comp (ref "Y2")
      (value "ABM7-16.000MHZ-D2Y-T")
      (footprint "16mhz_crystal")
      (description "CRYSTAL 16.0000MHZ 18PF SMD")
      (fields (field (name "MANUFACTURER") "Abracon") (field (name "TOLERANCE") "20ppm"))
      (libsource (lib "Schlib1") (part "ABM7-16.000MHZ-D2Y-T"))
    )
    (comp (ref "Z1")
      (value "CG0603MLC-05E")
      (footprint "R0603")
      (description "VARISTOR 0603")
      (fields (field (name "MANUFACTURER") "Bourns") (field (name "VOLTAGE") "5V"))
      (libsource (lib "Schlib1") (part "CG0603MLC-05E"))
    )
    (comp (ref "Z2")
      (value "CG0603MLC-05E")
      (footprint "R0603")
      (description "VARISTOR 0603")
      (fields (field (name "MANUFACTURER") "Bourns") (field (name "VOLTAGE") "5V"))
      (libsource (lib "Schlib1") (part "CG0603MLC-05E"))
    )
  )
  (nets
    (net (code "1") (name "+3V3") (class "Default")
      (node (ref "C13") (pin "2") (pinfunction "2_2") (pintype "passive"))
      (node (ref "C16") (pin "2") (pinfunction "2_2") (pintype "passive"))
      (node (ref "J1") (pin "4") (pinfunction "4_4") (pintype "passive"))
      (node (ref "JP4") (pin "3") (pinfunction "3_3") (pintype "passive"))
      (node (ref "R28") (pin "2") (pinfunction "2_2") (pintype "passive"))
      (node (ref "U3") (pin "4") (pinfunction "OUT_4") (pintype "passive"))
      (node (ref "U3") (pin "5") (pinfunction "SENSE_5") (pintype "passive"))
    )
    (net (code "2") (name "+5V") (class "Default")
      (node (ref "C12") (pin "2") (pinfunction "2_2") (pintype "passive"))
      (node (ref "C14") (pin "2") (pinfunction "2_2") (pintype "passive"))
      (node (ref "C2") (pin "1") (pinfunction "1_1") (pintype "passive"))
      (node (ref "C6") (pin "2") (pinfunction "2_2") (pintype "passive"))
      (node (ref "J1") (pin "5") (pinfunction "5_5") (pintype "passive"))
      (node (ref "J8") (pin "1") (pinfunction "1_1") (pintype "passive"))
      (node (ref "JP4") (pin "1") (pinfunction "1_1") (pintype "passive"))
      (node (ref "L1") (pin "2") (pinfunction "2_2") (pintype "passive"))
      (node (ref "R27") (pin "1") (pinfunction "1_1") (pintype "passive"))
      (node (ref "U2") (pin "31") (pinfunction "UVCC_31") (pintype "passive"))
      (node (ref "U3") (pin "1") (pinfunction "~{SHD}N_1") (pintype "passive"))
      (node (ref "U3") (pin "2") (pinfunction "IN_2") (pintype "passive"))
    )
    (net (code "3") (name "+5V{slash}3V3") (class "Default")
      (node (ref "C15") (pin "2") (pinfunction "2_2") (pintype "passive"))
      (node (ref "C17") (pin "2") (pinfunction "2_2") (pintype "passive"))
      (node (ref "C26") (pin "2") (pinfunction "2_2") (pintype "passive"))
      (node (ref "C28") (pin "2") (pinfunction "2_2") (pintype "passive"))
      (node (ref "C29") (pin "2") (pinfunction "2_2") (pintype "passive"))
      (node (ref "C30") (pin "2") (pinfunction "2_2") (pintype "passive"))
      (node (ref "C34") (pin "2") (pinfunction "2_2") (pintype "passive"))
      (node (ref "C8") (pin "2") (pinfunction "2_2") (pintype "passive"))
      (node (ref "D5") (pin "1") (pinfunction "CATHODE_1") (pintype "passive"))
      (node (ref "D6") (pin "1") (pinfunction "CATHODE_1") (pintype "passive"))
      (node (ref "FB1") (pin "1") (pinfunction "1_1") (pintype "passive"))
      (node (ref "FB2") (pin "1") (pinfunction "1_1") (pintype "passive"))
      (node (ref "FB3") (pin "1") (pinfunction "1_1") (pintype "passive"))
      (node (ref "J1") (pin "2") (pinfunction "2_2") (pintype "passive"))
      (node (ref "J5") (pin "2") (pinfunction "2_2") (pintype "passive"))
      (node (ref "J6") (pin "2") (pinfunction "2_2") (pintype "passive"))
      (node (ref "JP4") (pin "2") (pinfunction "2_2") (pintype "passive"))
      (node (ref "R1") (pin "2") (pinfunction "2_2") (pintype "passive"))
      (node (ref "R14") (pin "2") (pinfunction "2_2") (pintype "passive"))
      (node (ref "R15") (pin "2") (pinfunction "2_2") (pintype "passive"))
      (node (ref "R17") (pin "2") (pinfunction "2_2") (pintype "passive"))
      (node (ref "R18") (pin "2") (pinfunction "2_2") (pintype "passive"))
      (node (ref "R19") (pin "2") (pinfunction "2_2") (pintype "passive"))
      (node (ref "R2") (pin "2") (pinfunction "2_2") (pintype "passive"))
      (node (ref "R20") (pin "2") (pinfunction "2_2") (pintype "passive"))
      (node (ref "R21") (pin "2") (pinfunction "2_2") (pintype "passive"))
      (node (ref "R27") (pin "2") (pinfunction "2_2") (pintype "passive"))
      (node (ref "R28") (pin "1") (pinfunction "1_1") (pintype "passive"))
      (node (ref "R3") (pin "2") (pinfunction "2_2") (pintype "passive"))
      (node (ref "R4") (pin "2") (pinfunction "2_2") (pintype "passive"))
      (node (ref "U4") (pin "5") (pinfunction "5_5") (pintype "passive"))
      (node (ref "U5") (pin "5") (pinfunction "5_5") (pintype "passive"))
      (node (ref "U6") (pin "5") (pinfunction "5_5") (pintype "passive"))
      (node (ref "U7") (pin "5") (pinfunction "5_5") (pintype "passive"))
    )
    (net (code "4") (name "+AREF") (class "Default")
      (node (ref "C21") (pin "2") (pinfunction "2_2") (pintype "passive"))
      (node (ref "C24") (pin "2") (pinfunction "2_2") (pintype "passive"))
      (node (ref "J4") (pin "8") (pinfunction "8_8") (pintype "passive"))
      (node (ref "U1") (pin "21") (pinfunction "AREF_21") (pintype "passive"))
    )
    (net (code "5") (name "/+3V3_16U2_UCAP") (class "Default")
      (node (ref "C7") (pin "2") (pinfunction "2_2") (pintype "passive"))
      (node (ref "R26") (pin "1") (pinfunction "1_1") (pintype "passive"))
      (node (ref "U2") (pin "27") (pinfunction "UCAP_27") (pintype "passive"))
    )
    (net (code "6") (name "/+5V_USB") (class "Default")
      (node (ref "C1") (pin "1") (pinfunction "1_1") (pintype "passive"))
      (node (ref "J7") (pin "1") (pinfunction "1_1") (pintype "passive"))
      (node (ref "L1") (pin "1") (pinfunction "1_1") (pintype "passive"))
    )
    (net (code "7") (name "/+5V{slash}3V3_16U2") (class "Default")
      (node (ref "C3") (pin "2") (pinfunction "2_2") (pintype "passive"))
      (node (ref "C4") (pin "2") (pinfunction "2_2") (pintype "passive"))
      (node (ref "C5") (pin "2") (pinfunction "2_2") (pintype "passive"))
      (node (ref "FB1") (pin "2") (pinfunction "2_2") (pintype "passive"))
      (node (ref "R26") (pin "2") (pinfunction "2_2") (pintype "passive"))
      (node (ref "U2") (pin "32") (pinfunction "AVCC_32") (pintype "passive"))
      (node (ref "U2") (pin "4") (pinfunction "VCC_4") (pintype "passive"))
    )
    (net (code "8") (name "/+5V{slash}3V3_328P_AVCC") (class "Default")
      (node (ref "C22") (pin "2") (pinfunction "2_2") (pintype "passive"))
      (node (ref "C23") (pin "2") (pinfunction "2_2") (pintype "passive"))
      (node (ref "FB3") (pin "2") (pinfunction "2_2") (pintype "passive"))
      (node (ref "U1") (pin "20") (pinfunction "AVCC_20") (pintype "passive"))
    )
    (net (code "9") (name "/+5V{slash}3V3_328P_VCC") (class "Default")
      (node (ref "C19") (pin "2") (pinfunction "2_2") (pintype "passive"))
      (node (ref "C20") (pin "2") (pinfunction "2_2") (pintype "passive"))
      (node (ref "FB2") (pin "2") (pinfunction "2_2") (pintype "passive"))
      (node (ref "U1") (pin "7") (pinfunction "VCC_7") (pintype "passive"))
    )
    (net (code "10") (name "/16U2PROG_328P_RESETn") (class "Default")
      (node (ref "JP1") (pin "2") (pinfunction "2_2") (pintype "passive"))
      (node (ref "R1") (pin "1") (pinfunction "1_1") (pintype "passive"))
      (node (ref "U2") (pin "13") (pinfunction "/_HWB_/_AIN6_/_T0_/_INT7)_PD7_13") (pintype "passive"))
    )
    (net (code "11") (name "/16U2_16MHZ_XTAL1") (class "Default")
      (node (ref "C10") (pin "2") (pinfunction "2_2") (pintype "passive"))
      (node (ref "R9") (pin "1") (pinfunction "1_1") (pintype "passive"))
      (node (ref "U2") (pin "1") (pinfunction "XTAL1_1") (pintype "passive"))
      (node (ref "Y2") (pin "1") (pinfunction "1_1") (pintype "passive"))
    )
    (net (code "12") (name "/16U2_16MHZ_XTAL2") (class "Default")
      (node (ref "C9") (pin "2") (pinfunction "2_2") (pintype "passive"))
      (node (ref "R9") (pin "2") (pinfunction "2_2") (pintype "passive"))
      (node (ref "U2") (pin "2") (pinfunction "(PC0)_XTAL2_2") (pintype "passive"))
    )
    (net (code "13") (name "/16U2_BUF_RESETn") (class "Default")
      (node (ref "C31") (pin "2") (pinfunction "2_2") (pintype "passive"))
      (node (ref "R23") (pin "2") (pinfunction "2_2") (pintype "passive"))
      (node (ref "U5") (pin "1") (pinfunction "1_1") (pintype "passive"))
      (node (ref "U5") (pin "2") (pinfunction "2_2") (pintype "passive"))
    )
    (net (code "14") (name "/16U2_HDR_RESETn") (class "Default")
      (node (ref "J6") (pin "5") (pinfunction "5_5") (pintype "passive"))
      (node (ref "JP3") (pin "3") (pinfunction "3_3") (pintype "passive"))
    )
    (net (code "15") (name "/16U2_MISO") (class "Default")
      (node (ref "J6") (pin "1") (pinfunction "1_1") (pintype "passive"))
      (node (ref "U2") (pin "17") (pinfunction "PB3_(PDO_/_MISO_/_PCINT3)_17") (pintype "passive"))
    )
    (net (code "16") (name "/16U2_MOSI") (class "Default")
      (node (ref "J6") (pin "4") (pinfunction "4_4") (pintype "passive"))
      (node (ref "U2") (pin "16") (pinfunction "(PDI_/_MOSI_/_PCINT2)_PB2_16") (pintype "passive"))
    )
    (net (code "17") (name "/16U2_PB4") (class "Default")
      (node (ref "JP2") (pin "1") (pinfunction "1_1") (pintype "passive"))
      (node (ref "JP3") (pin "2") (pinfunction "2_2") (pintype "passive"))
      (node (ref "U2") (pin "18") (pinfunction "PB4_(T1_/_PCINT4)_18") (pintype "passive"))
    )
    (net (code "18") (name "/16U2_PB5") (class "Default")
      (node (ref "JP2") (pin "3") (pinfunction "3_3") (pintype "passive"))
      (node (ref "U2") (pin "19") (pinfunction "PB5_(PCINT5)_19") (pintype "passive"))
    )
    (net (code "19") (name "/16U2_PB6") (class "Default")
      (node (ref "JP2") (pin "2") (pinfunction "2_2") (pintype "passive"))
      (node (ref "U2") (pin "20") (pinfunction "PB6_(PCINT6)_20") (pintype "passive"))
    )
    (net (code "20") (name "/16U2_PB7") (class "Default")
      (node (ref "JP2") (pin "4") (pinfunction "4_4") (pintype "passive"))
      (node (ref "U2") (pin "21") (pinfunction "PB7_(PCINT7_/_OC.0A_/_OC.1C)_21") (pintype "passive"))
    )
    (net (code "21") (name "/16U2_RESETn") (class "Default")
      (node (ref "JP3") (pin "4") (pinfunction "4_4") (pintype "passive"))
      (node (ref "R4") (pin "1") (pinfunction "1_1") (pintype "passive"))
      (node (ref "U2") (pin "24") (pinfunction "Reset_(PC1_/_dW)_24") (pintype "passive"))
      (node (ref "U5") (pin "4") (pinfunction "4_4") (pintype "passive"))
    )
    (net (code "22") (name "/16U2_RXD") (class "Default")
      (node (ref "R11") (pin "1") (pinfunction "1_1") (pintype "passive"))
      (node (ref "U2") (pin "8") (pinfunction "(RXD1_/_AIN1_/_INT2)_PD2_8") (pintype "passive"))
    )
    (net (code "23") (name "/16U2_RX_LED") (class "Default")
      (node (ref "D4") (pin "1") (pinfunction "CATHODE_1") (pintype "passive"))
      (node (ref "U2") (pin "10") (pinfunction "(INT5/_AIN3)_PD4_10") (pintype "passive"))
    )
    (net (code "24") (name "/16U2_SCLK") (class "Default")
      (node (ref "J6") (pin "3") (pinfunction "3_3") (pintype "passive"))
      (node (ref "R5") (pin "2") (pinfunction "2_2") (pintype "passive"))
    )
    (net (code "25") (name "/16U2_SCLK_R") (class "Default")
      (node (ref "R5") (pin "1") (pinfunction "1_1") (pintype "passive"))
      (node (ref "U2") (pin "15") (pinfunction "(SCLK_/_PCINT1)_PB1_15") (pintype "passive"))
    )
    (net (code "26") (name "/16U2_TXD") (class "Default")
      (node (ref "R10") (pin "1") (pinfunction "1_1") (pintype "passive"))
      (node (ref "U2") (pin "9") (pinfunction "(TXD1_/_INT3)_PD3_9") (pintype "passive"))
    )
    (net (code "27") (name "/16U2_TX_LED") (class "Default")
      (node (ref "D3") (pin "1") (pinfunction "CATHODE_1") (pintype "passive"))
      (node (ref "U2") (pin "11") (pinfunction "(XCK_AIN4_/_PCINT12)_PD5_11") (pintype "passive"))
    )
    (net (code "28") (name "/328P_16MHZ_XTAL1") (class "Default")
      (node (ref "C27") (pin "2") (pinfunction "2_2") (pintype "passive"))
      (node (ref "R16") (pin "1") (pinfunction "1_1") (pintype "passive"))
      (node (ref "U1") (pin "9") (pinfunction "PB6/PCINT6/XTAL1/TOSC1_9") (pintype "passive"))
      (node (ref "Y1") (pin "1") (pinfunction "1_1") (pintype "passive"))
    )
    (net (code "29") (name "/328P_16MHZ_XTAL2") (class "Default")
      (node (ref "C25") (pin "2") (pinfunction "2_2") (pintype "passive"))
      (node (ref "R16") (pin "2") (pinfunction "2_2") (pintype "passive"))
      (node (ref "U1") (pin "10") (pinfunction "PB7/PCINT7/XTAL2/TOSC2_10") (pintype "passive"))
    )
    (net (code "30") (name "/328P_AUTORESETn") (class "Default")
      (node (ref "C11") (pin "1") (pinfunction "1_1") (pintype "passive"))
      (node (ref "R18") (pin "1") (pinfunction "1_1") (pintype "passive"))
      (node (ref "U6") (pin "1") (pinfunction "1_1") (pintype "passive"))
    )
    (net (code "31") (name "/328P_BUF_RESETn") (class "Default")
      (node (ref "C32") (pin "2") (pinfunction "2_2") (pintype "passive"))
      (node (ref "R24") (pin "2") (pinfunction "2_2") (pintype "passive"))
      (node (ref "U6") (pin "2") (pinfunction "2_2") (pintype "passive"))
    )
    (net (code "32") (name "/328P_RESETn") (class "Default")
      (node (ref "J1") (pin "3") (pinfunction "3_3") (pintype "passive"))
      (node (ref "J5") (pin "5") (pinfunction "5_5") (pintype "passive"))
      (node (ref "JP3") (pin "1") (pinfunction "1_1") (pintype "passive"))
      (node (ref "R14") (pin "1") (pinfunction "1_1") (pintype "passive"))
      (node (ref "U1") (pin "1") (pinfunction "PC6/PCINT14/~{RESE}T_1") (pintype "passive"))
      (node (ref "U6") (pin "4") (pinfunction "4_4") (pintype "passive"))
    )
    (net (code "33") (name "/AD0") (class "Default")
      (node (ref "J2") (pin "1") (pinfunction "1_1") (pintype "passive"))
      (node (ref "U1") (pin "23") (pinfunction "ADC0/PCINT8/PC0_23") (pintype "passive"))
    )
    (net (code "34") (name "/AD1") (class "Default")
      (node (ref "J2") (pin "2") (pinfunction "2_2") (pintype "passive"))
      (node (ref "U1") (pin "24") (pinfunction "ADC1/PCINT9/PC1_24") (pintype "passive"))
    )
    (net (code "35") (name "/AD2") (class "Default")
      (node (ref "J2") (pin "3") (pinfunction "3_3") (pintype "passive"))
      (node (ref "U1") (pin "25") (pinfunction "ADC2/PCINT10/PC2_25") (pintype "passive"))
    )
    (net (code "36") (name "/AD3") (class "Default")
      (node (ref "J2") (pin "4") (pinfunction "4_4") (pintype "passive"))
      (node (ref "U1") (pin "26") (pinfunction "ADC3/PCINT11/PC3_26") (pintype "passive"))
    )
    (net (code "37") (name "/AD4{slash}SDA") (class "Default")
      (node (ref "J2") (pin "5") (pinfunction "5_5") (pintype "passive"))
      (node (ref "J4") (pin "9") (pinfunction "9_9") (pintype "passive"))
      (node (ref "U1") (pin "27") (pinfunction "ADC4/SDA/PCINT12/PC4_27") (pintype "passive"))
    )
    (net (code "38") (name "/AD5{slash}SCL") (class "Default")
      (node (ref "J2") (pin "6") (pinfunction "6_6") (pintype "passive"))
      (node (ref "J4") (pin "10") (pinfunction "10_10") (pintype "passive"))
      (node (ref "U1") (pin "28") (pinfunction "ADC5/SCL/PCINT13/PC5_28") (pintype "passive"))
    )
    (net (code "39") (name "/BUTTON_RESETn") (class "Default")
      (node (ref "D6") (pin "2") (pinfunction "ANODE_2") (pintype "passive"))
      (node (ref "R20") (pin "1") (pinfunction "1_1") (pintype "passive"))
      (node (ref "R24") (pin "1") (pinfunction "1_1") (pintype "passive"))
      (node (ref "SW1") (pin "1") (pinfunction "1_1") (pintype "passive"))
      (node (ref "SW1") (pin "2") (pinfunction "2_2") (pintype "passive"))
    )
    (net (code "40") (name "/CON_USB_N") (class "Default")
      (node (ref "J7") (pin "2") (pinfunction "2_2") (pintype "passive"))
      (node (ref "R6") (pin "1") (pinfunction "1_1") (pintype "passive"))
      (node (ref "Z1") (pin "2") (pinfunction "2_2") (pintype "passive"))
    )
    (net (code "41") (name "/CON_USB_P") (class "Default")
      (node (ref "J7") (pin "3") (pinfunction "3_3") (pintype "passive"))
      (node (ref "R7") (pin "1") (pinfunction "1_1") (pintype "passive"))
      (node (ref "Z2") (pin "2") (pinfunction "2_2") (pintype "passive"))
    )
    (net (code "42") (name "/IO0") (class "Default")
      (node (ref "J3") (pin "1") (pinfunction "1_1") (pintype "passive"))
      (node (ref "R10") (pin "2") (pinfunction "2_2") (pintype "passive"))
      (node (ref "U1") (pin "2") (pinfunction "PCINT16/RXD/PD0_2") (pintype "passive"))
    )
    (net (code "43") (name "/IO1") (class "Default")
      (node (ref "J3") (pin "2") (pinfunction "2_2") (pintype "passive"))
      (node (ref "R11") (pin "2") (pinfunction "2_2") (pintype "passive"))
      (node (ref "U1") (pin "3") (pinfunction "PCINT17/TXD/_PD1_3") (pintype "passive"))
    )
    (net (code "44") (name "/IO2") (class "Default")
      (node (ref "J3") (pin "3") (pinfunction "3_3") (pintype "passive"))
      (node (ref "U1") (pin "4") (pinfunction "PCINT18/INT0/PD2_4") (pintype "passive"))
    )
    (net (code "45") (name "/IO3") (class "Default")
      (node (ref "J3") (pin "4") (pinfunction "4_4") (pintype "passive"))
      (node (ref "U1") (pin "5") (pinfunction "PCINT19/OC2B/INT1/PD3_5") (pintype "passive"))
    )
    (net (code "46") (name "/IO4") (class "Default")
      (node (ref "J3") (pin "5") (pinfunction "5_5") (pintype "passive"))
      (node (ref "U1") (pin "6") (pinfunction "PCINT20/XCK/T0/PD4_6") (pintype "passive"))
    )
    (net (code "47") (name "/IO5") (class "Default")
      (node (ref "J3") (pin "6") (pinfunction "6_6") (pintype "passive"))
      (node (ref "U1") (pin "11") (pinfunction "PCINT21/OC0B/T1/PD5_11") (pintype "passive"))
    )
    (net (code "48") (name "/IO6") (class "Default")
      (node (ref "J3") (pin "7") (pinfunction "7_7") (pintype "passive"))
      (node (ref "U1") (pin "12") (pinfunction "PCINT22/OC0A/AIN0/PD6_12") (pintype "passive"))
    )
    (net (code "49") (name "/IO7") (class "Default")
      (node (ref "J3") (pin "8") (pinfunction "8_8") (pintype "passive"))
      (node (ref "U1") (pin "13") (pinfunction "PCINT23/AIN1/PD7_13") (pintype "passive"))
    )
    (net (code "50") (name "/IO8") (class "Default")
      (node (ref "J4") (pin "1") (pinfunction "1_1") (pintype "passive"))
      (node (ref "R22") (pin "2") (pinfunction "2_2") (pintype "passive"))
      (node (ref "U1") (pin "14") (pinfunction "PCINT0/CLKO/ICP1/PB0_14") (pintype "passive"))
    )
    (net (code "51") (name "/IO9") (class "Default")
      (node (ref "J4") (pin "2") (pinfunction "2_2") (pintype "passive"))
      (node (ref "U1") (pin "15") (pinfunction "OC1A/PCINT1/PB1_15") (pintype "passive"))
    )
    (net (code "52") (name "/MISO") (class "Default")
      (node (ref "J4") (pin "5") (pinfunction "5_5") (pintype "passive"))
      (node (ref "J5") (pin "1") (pinfunction "1_1") (pintype "passive"))
      (node (ref "U1") (pin "18") (pinfunction "MISO/PCINT4/_PB4_18") (pintype "passive"))
    )
    (net (code "53") (name "/MOSI") (class "Default")
      (node (ref "J4") (pin "4") (pinfunction "4_4") (pintype "passive"))
      (node (ref "J5") (pin "4") (pinfunction "4_4") (pintype "passive"))
      (node (ref "U1") (pin "17") (pinfunction "MOSI/OC2A/PCINT3/PB3_17") (pintype "passive"))
    )
    (net (code "54") (name "/SCK") (class "Default")
      (node (ref "J4") (pin "6") (pinfunction "6_6") (pintype "passive"))
      (node (ref "J5") (pin "3") (pinfunction "3_3") (pintype "passive"))
      (node (ref "R13") (pin "2") (pinfunction "2_2") (pintype "passive"))
      (node (ref "U4") (pin "1") (pinfunction "1_1") (pintype "passive"))
      (node (ref "U4") (pin "2") (pinfunction "2_2") (pintype "passive"))
    )
    (net (code "55") (name "/SCK_R") (class "Default")
      (node (ref "R13") (pin "1") (pinfunction "1_1") (pintype "passive"))
      (node (ref "U1") (pin "19") (pinfunction "SCK/PCINT5/PB5_19") (pintype "passive"))
    )
    (net (code "56") (name "/SS") (class "Default")
      (node (ref "J4") (pin "3") (pinfunction "3_3") (pintype "passive"))
      (node (ref "U1") (pin "16") (pinfunction "SS/OC1B/PCINT2/PB2_16") (pintype "passive"))
    )
    (net (code "57") (name "/USB_N") (class "Default")
      (node (ref "R6") (pin "2") (pinfunction "2_2") (pintype "passive"))
      (node (ref "U2") (pin "30") (pinfunction "D-_30") (pintype "passive"))
    )
    (net (code "58") (name "/USB_P") (class "Default")
      (node (ref "R7") (pin "2") (pinfunction "2_2") (pintype "passive"))
      (node (ref "U2") (pin "29") (pinfunction "D+_29") (pintype "passive"))
    )
    (net (code "59") (name "/USER_BUTTON") (class "Default")
      (node (ref "R21") (pin "1") (pinfunction "1_1") (pintype "passive"))
      (node (ref "R25") (pin "1") (pinfunction "1_1") (pintype "passive"))
      (node (ref "SW2") (pin "1") (pinfunction "1_1") (pintype "passive"))
      (node (ref "SW2") (pin "2") (pinfunction "2_2") (pintype "passive"))
    )
    (net (code "60") (name "/USER_BUTTON_BUF") (class "Default")
      (node (ref "C33") (pin "2") (pinfunction "2_2") (pintype "passive"))
      (node (ref "R25") (pin "2") (pinfunction "2_2") (pintype "passive"))
      (node (ref "U7") (pin "1") (pinfunction "1_1") (pintype "passive"))
      (node (ref "U7") (pin "2") (pinfunction "2_2") (pintype "passive"))
    )
    (net (code "61") (name "GND") (class "Default")
      (node (ref "C1") (pin "2") (pinfunction "2_2") (pintype "passive"))
      (node (ref "C10") (pin "1") (pinfunction "1_1") (pintype "passive"))
      (node (ref "C12") (pin "1") (pinfunction "1_1") (pintype "passive"))
      (node (ref "C13") (pin "1") (pinfunction "1_1") (pintype "passive"))
      (node (ref "C14") (pin "1") (pinfunction "1_1") (pintype "passive"))
      (node (ref "C15") (pin "1") (pinfunction "1_1") (pintype "passive"))
      (node (ref "C16") (pin "1") (pinfunction "1_1") (pintype "passive"))
      (node (ref "C17") (pin "1") (pinfunction "1_1") (pintype "passive"))
      (node (ref "C19") (pin "1") (pinfunction "1_1") (pintype "passive"))
      (node (ref "C2") (pin "2") (pinfunction "2_2") (pintype "passive"))
      (node (ref "C20") (pin "1") (pinfunction "1_1") (pintype "passive"))
      (node (ref "C21") (pin "1") (pinfunction "1_1") (pintype "passive"))
      (node (ref "C22") (pin "1") (pinfunction "1_1") (pintype "passive"))
      (node (ref "C23") (pin "1") (pinfunction "1_1") (pintype "passive"))
      (node (ref "C24") (pin "1") (pinfunction "1_1") (pintype "passive"))
      (node (ref "C25") (pin "1") (pinfunction "1_1") (pintype "passive"))
      (node (ref "C26") (pin "1") (pinfunction "1_1") (pintype "passive"))
      (node (ref "C27") (pin "1") (pinfunction "1_1") (pintype "passive"))
      (node (ref "C28") (pin "1") (pinfunction "1_1") (pintype "passive"))
      (node (ref "C29") (pin "1") (pinfunction "1_1") (pintype "passive"))
      (node (ref "C3") (pin "1") (pinfunction "1_1") (pintype "passive"))
      (node (ref "C30") (pin "1") (pinfunction "1_1") (pintype "passive"))
      (node (ref "C31") (pin "1") (pinfunction "1_1") (pintype "passive"))
      (node (ref "C32") (pin "1") (pinfunction "1_1") (pintype "passive"))
      (node (ref "C33") (pin "1") (pinfunction "1_1") (pintype "passive"))
      (node (ref "C34") (pin "1") (pinfunction "1_1") (pintype "passive"))
      (node (ref "C4") (pin "1") (pinfunction "1_1") (pintype "passive"))
      (node (ref "C5") (pin "1") (pinfunction "1_1") (pintype "passive"))
      (node (ref "C6") (pin "1") (pinfunction "1_1") (pintype "passive"))
      (node (ref "C7") (pin "1") (pinfunction "1_1") (pintype "passive"))
      (node (ref "C8") (pin "1") (pinfunction "1_1") (pintype "passive"))
      (node (ref "C9") (pin "1") (pinfunction "1_1") (pintype "passive"))
      (node (ref "D1") (pin "1") (pinfunction "CATHODE_1") (pintype "passive"))
      (node (ref "J1") (pin "6") (pinfunction "6_6") (pintype "passive"))
      (node (ref "J1") (pin "7") (pinfunction "7_7") (pintype "passive"))
      (node (ref "J4") (pin "7") (pinfunction "7_7") (pintype "passive"))
      (node (ref "J5") (pin "6") (pinfunction "6_6") (pintype "passive"))
      (node (ref "J6") (pin "6") (pinfunction "6_6") (pintype "passive"))
      (node (ref "J7") (pin "10") (pinfunction "10_10") (pintype "passive"))
      (node (ref "J7") (pin "11") (pinfunction "11_11") (pintype "passive"))
      (node (ref "J7") (pin "5") (pinfunction "5_5") (pintype "passive"))
      (node (ref "J7") (pin "6") (pinfunction "6_6") (pintype "passive"))
      (node (ref "J7") (pin "7") (pinfunction "7_7") (pintype "passive"))
      (node (ref "J7") (pin "8") (pinfunction "8_8") (pintype "passive"))
      (node (ref "J7") (pin "9") (pinfunction "9_9") (pintype "passive"))
      (node (ref "J9") (pin "1") (pinfunction "1_1") (pintype "passive"))
      (node (ref "MH1") (pin "1") (pinfunction "1_1") (pintype "passive"))
      (node (ref "MH2") (pin "1") (pinfunction "1_1") (pintype "passive"))
      (node (ref "MH3") (pin "1") (pinfunction "1_1") (pintype "passive"))
      (node (ref "R12") (pin "1") (pinfunction "1_1") (pintype "passive"))
      (node (ref "R8") (pin "2") (pinfunction "2_2") (pintype "passive"))
      (node (ref "SW1") (pin "3") (pinfunction "3_3") (pintype "passive"))
      (node (ref "SW1") (pin "4") (pinfunction "4_4") (pintype "passive"))
      (node (ref "SW2") (pin "3") (pinfunction "3_3") (pintype "passive"))
      (node (ref "SW2") (pin "4") (pinfunction "4_4") (pintype "passive"))
      (node (ref "U1") (pin "22") (pinfunction "GND_2_22") (pintype "passive"))
      (node (ref "U1") (pin "8") (pinfunction "GND_1_8") (pintype "passive"))
      (node (ref "U2") (pin "28") (pinfunction "UGND_28") (pintype "passive"))
      (node (ref "U2") (pin "3") (pinfunction "GND_3") (pintype "passive"))
      (node (ref "U3") (pin "3") (pinfunction "GND_3") (pintype "passive"))
      (node (ref "U3") (pin "6") (pinfunction "EPAD_6") (pintype "passive"))
      (node (ref "U4") (pin "3") (pinfunction "3_3") (pintype "passive"))
      (node (ref "U5") (pin "3") (pinfunction "3_3") (pintype "passive"))
      (node (ref "U6") (pin "3") (pinfunction "3_3") (pintype "passive"))
      (node (ref "U7") (pin "3") (pinfunction "3_3") (pintype "passive"))
      (node (ref "Z1") (pin "1") (pinfunction "1_1") (pintype "passive"))
      (node (ref "Z2") (pin "1") (pinfunction "1_1") (pintype "passive"))
    )
    (net (code "62") (name "Net-(C11-Pad2)") (class "Default")
      (node (ref "C11") (pin "2") (pinfunction "2_2") (pintype "passive"))
      (node (ref "JP1") (pin "1") (pinfunction "1_1") (pintype "passive"))
    )
    (net (code "63") (name "Net-(D1-ANODE)") (class "Default")
      (node (ref "D1") (pin "2") (pinfunction "ANODE_2") (pintype "passive"))
      (node (ref "R17") (pin "1") (pinfunction "1_1") (pintype "passive"))
    )
    (net (code "64") (name "Net-(D2-ANODE)") (class "Default")
      (node (ref "D2") (pin "2") (pinfunction "ANODE_2") (pintype "passive"))
      (node (ref "R15") (pin "1") (pinfunction "1_1") (pintype "passive"))
    )
    (net (code "65") (name "Net-(D2-CATHODE)") (class "Default")
      (node (ref "D2") (pin "1") (pinfunction "CATHODE_1") (pintype "passive"))
      (node (ref "U4") (pin "4") (pinfunction "4_4") (pintype "passive"))
    )
    (net (code "66") (name "Net-(D3-ANODE)") (class "Default")
      (node (ref "D3") (pin "2") (pinfunction "ANODE_2") (pintype "passive"))
      (node (ref "R2") (pin "1") (pinfunction "1_1") (pintype "passive"))
    )
    (net (code "67") (name "Net-(D4-ANODE)") (class "Default")
      (node (ref "D4") (pin "2") (pinfunction "ANODE_2") (pintype "passive"))
      (node (ref "R3") (pin "1") (pinfunction "1_1") (pintype "passive"))
    )
    (net (code "68") (name "Net-(D5-ANODE)") (class "Default")
      (node (ref "D5") (pin "2") (pinfunction "ANODE_2") (pintype "passive"))
      (node (ref "R19") (pin "1") (pinfunction "1_1") (pintype "passive"))
      (node (ref "R23") (pin "1") (pinfunction "1_1") (pintype "passive"))
    )
    (net (code "69") (name "Net-(J7-Pad4)") (class "Default")
      (node (ref "J7") (pin "4") (pinfunction "4_4") (pintype "passive"))
      (node (ref "R8") (pin "1") (pinfunction "1_1") (pintype "passive"))
    )
    (net (code "70") (name "Net-(JP1-Pad3)") (class "Default")
      (node (ref "JP1") (pin "3") (pinfunction "3_3") (pintype "passive"))
      (node (ref "R12") (pin "2") (pinfunction "2_2") (pintype "passive"))
    )
    (net (code "71") (name "Net-(R22-Pad1)") (class "Default")
      (node (ref "R22") (pin "1") (pinfunction "1_1") (pintype "passive"))
      (node (ref "U7") (pin "4") (pinfunction "4_4") (pintype "passive"))
    )
    (net (code "72") (name "unconnected-(J1-Pad1)") (class "Default")
      (node (ref "J1") (pin "1") (pinfunction "1_1") (pintype "passive+no_connect"))
    )
    (net (code "73") (name "unconnected-(J1-Pad8)") (class "Default")
      (node (ref "J1") (pin "8") (pinfunction "8_8") (pintype "passive+no_connect"))
    )
    (net (code "74") (name "unconnected-(MH4-Pad1)") (class "Default")
      (node (ref "MH4") (pin "1") (pinfunction "1_1") (pintype "passive+no_connect"))
    )
    (net (code "75") (name "unconnected-(U2-(AIN0_{slash}_INT1)_PD1-Pad7)") (class "Default")
      (node (ref "U2") (pin "7") (pinfunction "(AIN0_/_INT1)_PD1_7") (pintype "passive+no_connect"))
    )
    (net (code "76") (name "unconnected-(U2-(OC.0B_{slash}_INT0)_PD0-Pad6)") (class "Default")
      (node (ref "U2") (pin "6") (pinfunction "(OC.0B_/_INT0)_PD0_6") (pintype "passive+no_connect"))
    )
    (net (code "77") (name "unconnected-(U2-(PCINT11_{slash}AIN2_)_PC2-Pad5)") (class "Default")
      (node (ref "U2") (pin "5") (pinfunction "(PCINT11_/AIN2_)_PC2_5") (pintype "passive+no_connect"))
    )
    (net (code "78") (name "unconnected-(U2-(RTS_{slash}_AIN5_{slash}_INT6)_PD6-Pad12)") (class "Default")
      (node (ref "U2") (pin "12") (pinfunction "(RTS_/_AIN5_/_INT6)_PD6_12") (pintype "passive"))
    )
    (net (code "79") (name "unconnected-(U2-(SS_{slash}_PCINT0)_PB0-Pad14)") (class "Default")
      (node (ref "U2") (pin "14") (pinfunction "(SS_/_PCINT0)_PB0_14") (pintype "passive+no_connect"))
    )
    (net (code "80") (name "unconnected-(U2-PC4_(PCINT10)-Pad26)") (class "Default")
      (node (ref "U2") (pin "26") (pinfunction "PC4_(PCINT10)_26") (pintype "passive+no_connect"))
    )
    (net (code "81") (name "unconnected-(U2-PC5_(_PCINT9{slash}_OC.1B)-Pad25)") (class "Default")
      (node (ref "U2") (pin "25") (pinfunction "PC5_(_PCINT9/_OC.1B)_25") (pintype "passive+no_connect"))
    )
    (net (code "82") (name "unconnected-(U2-PC6_(OC.1A_{slash}_PCINT8)-Pad23)") (class "Default")
      (node (ref "U2") (pin "23") (pinfunction "PC6_(OC.1A_/_PCINT8)_23") (pintype "passive+no_connect"))
    )
    (net (code "83") (name "unconnected-(U2-PC7_(INT4_{slash}_ICP1_{slash}_CLKO)-Pad22)") (class "Default")
      (node (ref "U2") (pin "22") (pinfunction "PC7_(INT4_/_ICP1_/_CLKO)_22") (pintype "passive+no_connect"))
    )
    (net (code "84") (name "unconnected-(Y1-Pad2)") (class "Default")
      (node (ref "Y1") (pin "2") (pinfunction "2_2") (pintype "passive"))
    )
    (net (code "85") (name "unconnected-(Y2-Pad2)") (class "Default")
      (node (ref "Y2") (pin "2") (pinfunction "2_2") (pintype "passive"))
    )
  )
)
